# addons_Hbridge_shiftReg.net
KiCad netlist of a schematic drawn in Altium Designer
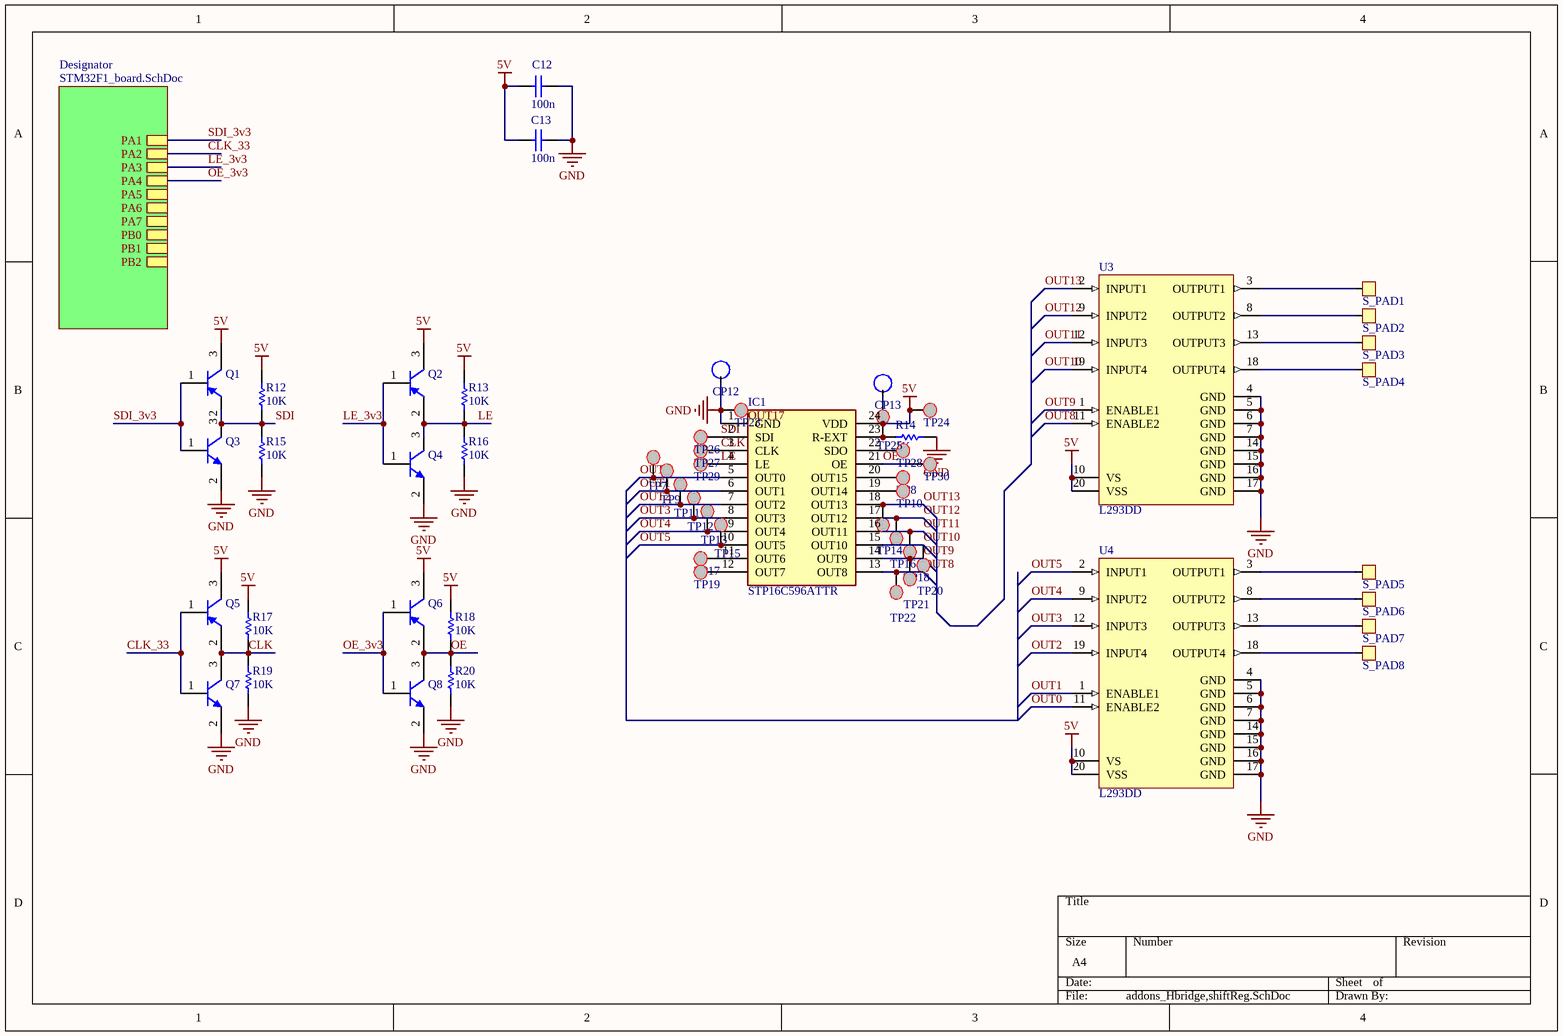
[diagram p0: addons_Hbridge,shiftReg.SchDoc]

(export (version "E")
  (design (tool "Eeschema 10.0.6"))
  (components
    (comp (ref "C12")
      (value "100n")
      (footprint "SMD-0603-RES")
      (description "Capacitor")
      (libsource (lib "Simulation Generic Components") (part "Capacitor"))
    )
    (comp (ref "C13")
      (value "100n")
      (footprint "SMD-0603-RES")
      (description "Capacitor")
      (libsource (lib "Simulation Generic Components") (part "Capacitor"))
    )
    (comp (ref "CP12")
      (value "CONNECT_PAD")
      (footprint "PAD_SQUARE")
      (libsource (lib "solderpad") (part "CONNECT_PAD"))
    )
    (comp (ref "CP13")
      (value "CONNECT_PAD")
      (footprint "PAD_SQUARE")
      (libsource (lib "solderpad") (part "CONNECT_PAD"))
    )
    (comp (ref "IC1")
      (value "STP16C596ATTR")
      (footprint "SamacSys:SOP65P638X110-24N")
      (description "Integrated Circuit")
      (libsource (lib "*") (part "STP16C596ATTR"))
    )
    (comp (ref "Q1")
      (value "BC807-40LT1G")
      (footprint "ONSC-SOT-23-3-318-08_V")
      (description "General Purpose Transistor, PNP Silicon, 3-Pin SOT-23, Pb-Free, Tape and Reel")
      (fields (field (name "MANUFACTURER") "On Semiconductor"))
      (libsource (lib "Altium Content Vault") (part "ONSC-PNP-B1E2C3-3"))
    )
    (comp (ref "Q2")
      (value "BC807-40LT1G")
      (footprint "ONSC-SOT-23-3-318-08_V")
      (description "General Purpose Transistor, PNP Silicon, 3-Pin SOT-23, Pb-Free, Tape and Reel")
      (fields (field (name "MANUFACTURER") "On Semiconductor"))
      (libsource (lib "Altium Content Vault") (part "ONSC-PNP-B1E2C3-3"))
    )
    (comp (ref "Q3")
      (value "MMBTA42LT1G")
      (footprint "ONSC-SOT-23-3-318-08_V")
      (description "High Voltage Transistor, NPN Silicon, 3-Pin SOT-23, Pb-Free, Tape and Reel")
      (fields (field (name "MANUFACTURER") "On Semiconductor"))
      (libsource (lib "Altium Content Vault") (part "ONSC-NPN-B1E2C3-3"))
    )
    (comp (ref "Q4")
      (value "MMBTA42LT1G")
      (footprint "ONSC-SOT-23-3-318-08_V")
      (description "High Voltage Transistor, NPN Silicon, 3-Pin SOT-23, Pb-Free, Tape and Reel")
      (fields (field (name "MANUFACTURER") "On Semiconductor"))
      (libsource (lib "Altium Content Vault") (part "ONSC-NPN-B1E2C3-3"))
    )
    (comp (ref "Q5")
      (value "BC807-40LT1G")
      (footprint "ONSC-SOT-23-3-318-08_V")
      (description "General Purpose Transistor, PNP Silicon, 3-Pin SOT-23, Pb-Free, Tape and Reel")
      (fields (field (name "MANUFACTURER") "On Semiconductor"))
      (libsource (lib "Altium Content Vault") (part "ONSC-PNP-B1E2C3-3"))
    )
    (comp (ref "Q6")
      (value "BC807-40LT1G")
      (footprint "ONSC-SOT-23-3-318-08_V")
      (description "General Purpose Transistor, PNP Silicon, 3-Pin SOT-23, Pb-Free, Tape and Reel")
      (fields (field (name "MANUFACTURER") "On Semiconductor"))
      (libsource (lib "Altium Content Vault") (part "ONSC-PNP-B1E2C3-3"))
    )
    (comp (ref "Q7")
      (value "MMBTA42LT1G")
      (footprint "ONSC-SOT-23-3-318-08_V")
      (description "High Voltage Transistor, NPN Silicon, 3-Pin SOT-23, Pb-Free, Tape and Reel")
      (fields (field (name "MANUFACTURER") "On Semiconductor"))
      (libsource (lib "Altium Content Vault") (part "ONSC-NPN-B1E2C3-3"))
    )
    (comp (ref "Q8")
      (value "MMBTA42LT1G")
      (footprint "ONSC-SOT-23-3-318-08_V")
      (description "High Voltage Transistor, NPN Silicon, 3-Pin SOT-23, Pb-Free, Tape and Reel")
      (fields (field (name "MANUFACTURER") "On Semiconductor"))
      (libsource (lib "Altium Content Vault") (part "ONSC-NPN-B1E2C3-3"))
    )
    (comp (ref "R12")
      (value "10K")
      (footprint "SMD-0603-RES")
      (description "Resistor")
      (libsource (lib "Simulation Generic Components") (part "Resistor"))
    )
    (comp (ref "R13")
      (value "10K")
      (footprint "SMD-0603-RES")
      (description "Resistor")
      (libsource (lib "Simulation Generic Components") (part "Resistor"))
    )
    (comp (ref "R14")
      (value "1K")
      (footprint "SMD-0603-RES")
      (description "Resistor")
      (libsource (lib "Simulation Generic Components") (part "Resistor"))
    )
    (comp (ref "R15")
      (value "10K")
      (footprint "SMD-0603-RES")
      (description "Resistor")
      (libsource (lib "Simulation Generic Components") (part "Resistor"))
    )
    (comp (ref "R16")
      (value "10K")
      (footprint "SMD-0603-RES")
      (description "Resistor")
      (libsource (lib "Simulation Generic Components") (part "Resistor"))
    )
    (comp (ref "R17")
      (value "10K")
      (footprint "SMD-0603-RES")
      (description "Resistor")
      (libsource (lib "Simulation Generic Components") (part "Resistor"))
    )
    (comp (ref "R18")
      (value "10K")
      (footprint "SMD-0603-RES")
      (description "Resistor")
      (libsource (lib "Simulation Generic Components") (part "Resistor"))
    )
    (comp (ref "R19")
      (value "10K")
      (footprint "SMD-0603-RES")
      (description "Resistor")
      (libsource (lib "Simulation Generic Components") (part "Resistor"))
    )
    (comp (ref "R20")
      (value "10K")
      (footprint "SMD-0603-RES")
      (description "Resistor")
      (libsource (lib "Simulation Generic Components") (part "Resistor"))
    )
    (comp (ref "S_PAD1")
      (value "SOLDER_PAD")
      (footprint "PAD_SQUARE")
      (libsource (lib "solderpad") (part "SOLDER_PAD"))
    )
    (comp (ref "S_PAD2")
      (value "SOLDER_PAD")
      (footprint "PAD_SQUARE")
      (libsource (lib "solderpad") (part "SOLDER_PAD"))
    )
    (comp (ref "S_PAD3")
      (value "SOLDER_PAD")
      (footprint "PAD_SQUARE")
      (libsource (lib "solderpad") (part "SOLDER_PAD"))
    )
    (comp (ref "S_PAD4")
      (value "SOLDER_PAD")
      (footprint "PAD_SQUARE")
      (libsource (lib "solderpad") (part "SOLDER_PAD"))
    )
    (comp (ref "S_PAD5")
      (value "SOLDER_PAD")
      (footprint "PAD_SQUARE")
      (libsource (lib "solderpad") (part "SOLDER_PAD"))
    )
    (comp (ref "S_PAD6")
      (value "SOLDER_PAD")
      (footprint "PAD_SQUARE")
      (libsource (lib "solderpad") (part "SOLDER_PAD"))
    )
    (comp (ref "S_PAD7")
      (value "SOLDER_PAD")
      (footprint "PAD_SQUARE")
      (libsource (lib "solderpad") (part "SOLDER_PAD"))
    )
    (comp (ref "S_PAD8")
      (value "SOLDER_PAD")
      (footprint "PAD_SQUARE")
      (libsource (lib "solderpad") (part "SOLDER_PAD"))
    )
    (comp (ref "TP7") (value "~") (footprint "ROUND_SMALL") (libsource (lib "solderpad") (part "TEST_PAD")))
    (comp (ref "TP8") (value "~") (footprint "ROUND_SMALL") (libsource (lib "solderpad") (part "TEST_PAD")))
    (comp (ref "TP9") (value "~") (footprint "ROUND_SMALL") (libsource (lib "solderpad") (part "TEST_PAD")))
    (comp (ref "TP10") (value "~") (footprint "ROUND_SMALL") (libsource (lib "solderpad") (part "TEST_PAD")))
    (comp (ref "TP11") (value "~") (footprint "ROUND_SMALL") (libsource (lib "solderpad") (part "TEST_PAD")))
    (comp (ref "TP12") (value "~") (footprint "ROUND_SMALL") (libsource (lib "solderpad") (part "TEST_PAD")))
    (comp (ref "TP13") (value "~") (footprint "ROUND_SMALL") (libsource (lib "solderpad") (part "TEST_PAD")))
    (comp (ref "TP14") (value "~") (footprint "ROUND_SMALL") (libsource (lib "solderpad") (part "TEST_PAD")))
    (comp (ref "TP15") (value "~") (footprint "ROUND_SMALL") (libsource (lib "solderpad") (part "TEST_PAD")))
    (comp (ref "TP16") (value "~") (footprint "ROUND_SMALL") (libsource (lib "solderpad") (part "TEST_PAD")))
    (comp (ref "TP17") (value "~") (footprint "ROUND_SMALL") (libsource (lib "solderpad") (part "TEST_PAD")))
    (comp (ref "TP18") (value "~") (footprint "ROUND_SMALL") (libsource (lib "solderpad") (part "TEST_PAD")))
    (comp (ref "TP19") (value "~") (footprint "ROUND_SMALL") (libsource (lib "solderpad") (part "TEST_PAD")))
    (comp (ref "TP20") (value "~") (footprint "ROUND_SMALL") (libsource (lib "solderpad") (part "TEST_PAD")))
    (comp (ref "TP21") (value "~") (footprint "ROUND_SMALL") (libsource (lib "solderpad") (part "TEST_PAD")))
    (comp (ref "TP22") (value "~") (footprint "ROUND_SMALL") (libsource (lib "solderpad") (part "TEST_PAD")))
    (comp (ref "TP23") (value "~") (footprint "ROUND_SMALL") (libsource (lib "solderpad") (part "TEST_PAD")))
    (comp (ref "TP24") (value "~") (footprint "ROUND_SMALL") (libsource (lib "solderpad") (part "TEST_PAD")))
    (comp (ref "TP25") (value "~") (footprint "ROUND_SMALL") (libsource (lib "solderpad") (part "TEST_PAD")))
    (comp (ref "TP26") (value "~") (footprint "ROUND_SMALL") (libsource (lib "solderpad") (part "TEST_PAD")))
    (comp (ref "TP27") (value "~") (footprint "ROUND_SMALL") (libsource (lib "solderpad") (part "TEST_PAD")))
    (comp (ref "TP28") (value "~") (footprint "ROUND_SMALL") (libsource (lib "solderpad") (part "TEST_PAD")))
    (comp (ref "TP29") (value "~") (footprint "ROUND_SMALL") (libsource (lib "solderpad") (part "TEST_PAD")))
    (comp (ref "TP30") (value "~") (footprint "ROUND_SMALL") (libsource (lib "solderpad") (part "TEST_PAD")))
    (comp (ref "U3")
      (value "L293DD")
      (footprint "STM-SOIC-20_M")
      (description "Push-Pull Four Channel Driver with Diodes, 4.5 to 36 V, 20-Pin SOIC, RoHS, Tube")
      (fields (field (name "TOLERANCE") "1%"))
      (libsource (lib "Altium Content Vault") (part "STM-L293DD-SO-20"))
    )
    (comp (ref "U4")
      (value "L293DD")
      (footprint "STM-SOIC-20_M")
      (description "Push-Pull Four Channel Driver with Diodes, 4.5 to 36 V, 20-Pin SOIC, RoHS, Tube")
      (fields (field (name "TOLERANCE") "1%"))
      (libsource (lib "Altium Content Vault") (part "STM-L293DD-SO-20"))
    )
  )
  (nets
    (net (code "1") (name "/CLK") (class "Default")
      (node (ref "IC1") (pin "3") (pinfunction "CLK_3") (pintype "passive"))
      (node (ref "Q5") (pin "2") (pinfunction "E_2") (pintype "passive"))
      (node (ref "Q7") (pin "3") (pinfunction "C_3") (pintype "passive"))
      (node (ref "R17") (pin "1") (pinfunction "1_1") (pintype "passive"))
      (node (ref "R19") (pin "2") (pinfunction "2_2") (pintype "passive"))
      (node (ref "TP27") (pin "1") (pinfunction "Test_Point_1") (pintype "passive"))
    )
    (net (code "2") (name "/CLK_33") (class "Default")
      (node (ref "Q5") (pin "1") (pinfunction "B_1") (pintype "passive"))
      (node (ref "Q7") (pin "1") (pinfunction "B_1") (pintype "passive"))
    )
    (net (code "3") (name "/LE") (class "Default")
      (node (ref "IC1") (pin "4") (pinfunction "LE_4") (pintype "passive"))
      (node (ref "Q2") (pin "2") (pinfunction "E_2") (pintype "passive"))
      (node (ref "Q4") (pin "3") (pinfunction "C_3") (pintype "passive"))
      (node (ref "R13") (pin "1") (pinfunction "1_1") (pintype "passive"))
      (node (ref "R16") (pin "2") (pinfunction "2_2") (pintype "passive"))
      (node (ref "TP29") (pin "1") (pinfunction "Test_Point_1") (pintype "passive"))
    )
    (net (code "4") (name "/LE_3v3") (class "Default")
      (node (ref "Q2") (pin "1") (pinfunction "B_1") (pintype "passive"))
      (node (ref "Q4") (pin "1") (pinfunction "B_1") (pintype "passive"))
    )
    (net (code "5") (name "/OE") (class "Default")
      (node (ref "IC1") (pin "21") (pinfunction "OE_21") (pintype "passive"))
      (node (ref "Q6") (pin "2") (pinfunction "E_2") (pintype "passive"))
      (node (ref "Q8") (pin "3") (pinfunction "C_3") (pintype "passive"))
      (node (ref "R18") (pin "1") (pinfunction "1_1") (pintype "passive"))
      (node (ref "R20") (pin "2") (pinfunction "2_2") (pintype "passive"))
      (node (ref "TP30") (pin "1") (pinfunction "Test_Point_1") (pintype "passive"))
    )
    (net (code "6") (name "/OE_3v3") (class "Default")
      (node (ref "Q6") (pin "1") (pinfunction "B_1") (pintype "passive"))
      (node (ref "Q8") (pin "1") (pinfunction "B_1") (pintype "passive"))
    )
    (net (code "7") (name "/OUT0") (class "Default")
      (node (ref "IC1") (pin "5") (pinfunction "OUT0_5") (pintype "passive"))
      (node (ref "TP7") (pin "1") (pinfunction "Test_Point_1") (pintype "passive"))
      (node (ref "U4") (pin "11") (pinfunction "ENABLE2_11") (pintype "input"))
    )
    (net (code "8") (name "/OUT1") (class "Default")
      (node (ref "IC1") (pin "6") (pinfunction "OUT1_6") (pintype "passive"))
      (node (ref "TP9") (pin "1") (pinfunction "Test_Point_1") (pintype "passive"))
      (node (ref "U4") (pin "1") (pinfunction "ENABLE1_1") (pintype "input"))
    )
    (net (code "9") (name "/OUT2") (class "Default")
      (node (ref "IC1") (pin "7") (pinfunction "OUT2_7") (pintype "passive"))
      (node (ref "TP11") (pin "1") (pinfunction "Test_Point_1") (pintype "passive"))
      (node (ref "U4") (pin "19") (pinfunction "INPUT4_19") (pintype "input"))
    )
    (net (code "10") (name "/OUT3") (class "Default")
      (node (ref "IC1") (pin "8") (pinfunction "OUT3_8") (pintype "passive"))
      (node (ref "TP12") (pin "1") (pinfunction "Test_Point_1") (pintype "passive"))
      (node (ref "U4") (pin "12") (pinfunction "INPUT3_12") (pintype "input"))
    )
    (net (code "11") (name "/OUT4") (class "Default")
      (node (ref "IC1") (pin "9") (pinfunction "OUT4_9") (pintype "passive"))
      (node (ref "TP13") (pin "1") (pinfunction "Test_Point_1") (pintype "passive"))
      (node (ref "U4") (pin "9") (pinfunction "INPUT2_9") (pintype "input"))
    )
    (net (code "12") (name "/OUT5") (class "Default")
      (node (ref "IC1") (pin "10") (pinfunction "OUT5_10") (pintype "passive"))
      (node (ref "TP15") (pin "1") (pinfunction "Test_Point_1") (pintype "passive"))
      (node (ref "U4") (pin "2") (pinfunction "INPUT1_2") (pintype "input"))
    )
    (net (code "13") (name "/OUT8") (class "Default")
      (node (ref "IC1") (pin "13") (pinfunction "OUT8_13") (pintype "passive"))
      (node (ref "TP22") (pin "1") (pinfunction "Test_Point_1") (pintype "passive"))
      (node (ref "U3") (pin "11") (pinfunction "ENABLE2_11") (pintype "input"))
    )
    (net (code "14") (name "/OUT9") (class "Default")
      (node (ref "IC1") (pin "14") (pinfunction "OUT9_14") (pintype "passive"))
      (node (ref "TP21") (pin "1") (pinfunction "Test_Point_1") (pintype "passive"))
      (node (ref "U3") (pin "1") (pinfunction "ENABLE1_1") (pintype "input"))
    )
    (net (code "15") (name "/OUT10") (class "Default")
      (node (ref "IC1") (pin "15") (pinfunction "OUT10_15") (pintype "passive"))
      (node (ref "TP20") (pin "1") (pinfunction "Test_Point_1") (pintype "passive"))
      (node (ref "U3") (pin "19") (pinfunction "INPUT4_19") (pintype "input"))
    )
    (net (code "16") (name "/OUT11") (class "Default")
      (node (ref "IC1") (pin "16") (pinfunction "OUT11_16") (pintype "passive"))
      (node (ref "TP18") (pin "1") (pinfunction "Test_Point_1") (pintype "passive"))
      (node (ref "U3") (pin "12") (pinfunction "INPUT3_12") (pintype "input"))
    )
    (net (code "17") (name "/OUT12") (class "Default")
      (node (ref "IC1") (pin "17") (pinfunction "OUT12_17") (pintype "passive"))
      (node (ref "TP16") (pin "1") (pinfunction "Test_Point_1") (pintype "passive"))
      (node (ref "U3") (pin "9") (pinfunction "INPUT2_9") (pintype "input"))
    )
    (net (code "18") (name "/OUT13") (class "Default")
      (node (ref "IC1") (pin "18") (pinfunction "OUT13_18") (pintype "passive"))
      (node (ref "TP14") (pin "1") (pinfunction "Test_Point_1") (pintype "passive"))
      (node (ref "U3") (pin "2") (pinfunction "INPUT1_2") (pintype "input"))
    )
    (net (code "26") (name "/SDI") (class "Default")
      (node (ref "IC1") (pin "2") (pinfunction "SDI_2") (pintype "passive"))
      (node (ref "Q1") (pin "2") (pinfunction "E_2") (pintype "passive"))
      (node (ref "Q3") (pin "3") (pinfunction "C_3") (pintype "passive"))
      (node (ref "R12") (pin "1") (pinfunction "1_1") (pintype "passive"))
      (node (ref "R15") (pin "2") (pinfunction "2_2") (pintype "passive"))
      (node (ref "TP26") (pin "1") (pinfunction "Test_Point_1") (pintype "passive"))
    )
    (net (code "27") (name "/SDI_3v3") (class "Default")
      (node (ref "Q1") (pin "1") (pinfunction "B_1") (pintype "passive"))
      (node (ref "Q3") (pin "1") (pinfunction "B_1") (pintype "passive"))
    )
    (net (code "28") (name "5V") (class "Default")
      (node (ref "C12") (pin "1") (pinfunction "1_1") (pintype "passive"))
      (node (ref "C13") (pin "1") (pinfunction "1_1") (pintype "passive"))
      (node (ref "CP13") (pin "1") (pinfunction "1_1") (pintype "passive"))
      (node (ref "IC1") (pin "24") (pinfunction "VDD_24") (pintype "passive"))
      (node (ref "Q1") (pin "3") (pinfunction "C_3") (pintype "passive"))
      (node (ref "Q2") (pin "3") (pinfunction "C_3") (pintype "passive"))
      (node (ref "Q5") (pin "3") (pinfunction "C_3") (pintype "passive"))
      (node (ref "Q6") (pin "3") (pinfunction "C_3") (pintype "passive"))
      (node (ref "R12") (pin "2") (pinfunction "2_2") (pintype "passive"))
      (node (ref "R13") (pin "2") (pinfunction "2_2") (pintype "passive"))
      (node (ref "R17") (pin "2") (pinfunction "2_2") (pintype "passive"))
      (node (ref "R18") (pin "2") (pinfunction "2_2") (pintype "passive"))
      (node (ref "TP24") (pin "1") (pinfunction "Test_Point_1") (pintype "passive"))
      (node (ref "U3") (pin "10") (pinfunction "VS_10") (pintype "power_in"))
      (node (ref "U3") (pin "20") (pinfunction "VSS_20") (pintype "power_in"))
      (node (ref "U4") (pin "10") (pinfunction "VS_10") (pintype "power_in"))
      (node (ref "U4") (pin "20") (pinfunction "VSS_20") (pintype "power_in"))
    )
    (net (code "29") (name "GND") (class "Default")
      (node (ref "C12") (pin "2") (pinfunction "2_2") (pintype "passive"))
      (node (ref "C13") (pin "2") (pinfunction "2_2") (pintype "passive"))
      (node (ref "CP12") (pin "1") (pinfunction "1_1") (pintype "passive"))
      (node (ref "IC1") (pin "1") (pinfunction "GND_1") (pintype "passive"))
      (node (ref "Q3") (pin "2") (pinfunction "E_2") (pintype "passive"))
      (node (ref "Q4") (pin "2") (pinfunction "E_2") (pintype "passive"))
      (node (ref "Q7") (pin "2") (pinfunction "E_2") (pintype "passive"))
      (node (ref "Q8") (pin "2") (pinfunction "E_2") (pintype "passive"))
      (node (ref "R14") (pin "2") (pinfunction "2_2") (pintype "passive"))
      (node (ref "R15") (pin "1") (pinfunction "1_1") (pintype "passive"))
      (node (ref "R16") (pin "1") (pinfunction "1_1") (pintype "passive"))
      (node (ref "R19") (pin "1") (pinfunction "1_1") (pintype "passive"))
      (node (ref "R20") (pin "1") (pinfunction "1_1") (pintype "passive"))
      (node (ref "TP23") (pin "1") (pinfunction "Test_Point_1") (pintype "passive"))
      (node (ref "U3") (pin "14") (pinfunction "GND_14") (pintype "power_in"))
      (node (ref "U3") (pin "15") (pinfunction "GND_15") (pintype "power_in"))
      (node (ref "U3") (pin "16") (pinfunction "GND_16") (pintype "power_in"))
      (node (ref "U3") (pin "17") (pinfunction "GND_17") (pintype "power_in"))
      (node (ref "U3") (pin "4") (pinfunction "GND_4") (pintype "power_in"))
      (node (ref "U3") (pin "5") (pinfunction "GND_5") (pintype "power_in"))
      (node (ref "U3") (pin "6") (pinfunction "GND_6") (pintype "power_in"))
      (node (ref "U3") (pin "7") (pinfunction "GND_7") (pintype "power_in"))
      (node (ref "U4") (pin "14") (pinfunction "GND_14") (pintype "power_in"))
      (node (ref "U4") (pin "15") (pinfunction "GND_15") (pintype "power_in"))
      (node (ref "U4") (pin "16") (pinfunction "GND_16") (pintype "power_in"))
      (node (ref "U4") (pin "17") (pinfunction "GND_17") (pintype "power_in"))
      (node (ref "U4") (pin "4") (pinfunction "GND_4") (pintype "power_in"))
      (node (ref "U4") (pin "5") (pinfunction "GND_5") (pintype "power_in"))
      (node (ref "U4") (pin "6") (pinfunction "GND_6") (pintype "power_in"))
      (node (ref "U4") (pin "7") (pinfunction "GND_7") (pintype "power_in"))
    )
    (net (code "30") (name "Net-(IC1-OUT6)") (class "Default")
      (node (ref "IC1") (pin "11") (pinfunction "OUT6_11") (pintype "passive"))
      (node (ref "TP17") (pin "1") (pinfunction "Test_Point_1") (pintype "passive"))
    )
    (net (code "31") (name "Net-(IC1-OUT7)") (class "Default")
      (node (ref "IC1") (pin "12") (pinfunction "OUT7_12") (pintype "passive"))
      (node (ref "TP19") (pin "1") (pinfunction "Test_Point_1") (pintype "passive"))
    )
    (net (code "32") (name "Net-(IC1-OUT14)") (class "Default")
      (node (ref "IC1") (pin "19") (pinfunction "OUT14_19") (pintype "passive"))
      (node (ref "TP10") (pin "1") (pinfunction "Test_Point_1") (pintype "passive"))
    )
    (net (code "33") (name "Net-(IC1-OUT15)") (class "Default")
      (node (ref "IC1") (pin "20") (pinfunction "OUT15_20") (pintype "passive"))
      (node (ref "TP8") (pin "1") (pinfunction "Test_Point_1") (pintype "passive"))
    )
    (net (code "34") (name "Net-(IC1-R-EXT)") (class "Default")
      (node (ref "IC1") (pin "23") (pinfunction "R-EXT_23") (pintype "passive"))
      (node (ref "R14") (pin "1") (pinfunction "1_1") (pintype "passive"))
      (node (ref "TP25") (pin "1") (pinfunction "Test_Point_1") (pintype "passive"))
    )
    (net (code "35") (name "Net-(IC1-SDO)") (class "Default")
      (node (ref "IC1") (pin "22") (pinfunction "SDO_22") (pintype "passive"))
      (node (ref "TP28") (pin "1") (pinfunction "Test_Point_1") (pintype "passive"))
    )
    (net (code "36") (name "Net-(S_PAD1-0)") (class "Default")
      (node (ref "S_PAD1") (pin "1") (pinfunction "0_1") (pintype "passive"))
      (node (ref "U3") (pin "3") (pinfunction "OUTPUT1_3") (pintype "output"))
    )
    (net (code "37") (name "Net-(S_PAD2-0)") (class "Default")
      (node (ref "S_PAD2") (pin "1") (pinfunction "0_1") (pintype "passive"))
      (node (ref "U3") (pin "8") (pinfunction "OUTPUT2_8") (pintype "output"))
    )
    (net (code "38") (name "Net-(S_PAD3-0)") (class "Default")
      (node (ref "S_PAD3") (pin "1") (pinfunction "0_1") (pintype "passive"))
      (node (ref "U3") (pin "13") (pinfunction "OUTPUT3_13") (pintype "output"))
    )
    (net (code "39") (name "Net-(S_PAD4-0)") (class "Default")
      (node (ref "S_PAD4") (pin "1") (pinfunction "0_1") (pintype "passive"))
      (node (ref "U3") (pin "18") (pinfunction "OUTPUT4_18") (pintype "output"))
    )
    (net (code "40") (name "Net-(S_PAD5-0)") (class "Default")
      (node (ref "S_PAD5") (pin "1") (pinfunction "0_1") (pintype "passive"))
      (node (ref "U4") (pin "3") (pinfunction "OUTPUT1_3") (pintype "output"))
    )
    (net (code "41") (name "Net-(S_PAD6-0)") (class "Default")
      (node (ref "S_PAD6") (pin "1") (pinfunction "0_1") (pintype "passive"))
      (node (ref "U4") (pin "8") (pinfunction "OUTPUT2_8") (pintype "output"))
    )
    (net (code "42") (name "Net-(S_PAD7-0)") (class "Default")
      (node (ref "S_PAD7") (pin "1") (pinfunction "0_1") (pintype "passive"))
      (node (ref "U4") (pin "13") (pinfunction "OUTPUT3_13") (pintype "output"))
    )
    (net (code "43") (name "Net-(S_PAD8-0)") (class "Default")
      (node (ref "S_PAD8") (pin "1") (pinfunction "0_1") (pintype "passive"))
      (node (ref "U4") (pin "18") (pinfunction "OUTPUT4_18") (pintype "output"))
    )
  )
)
